# Peripherals_-_USB.net
KiCad netlist of a schematic drawn in Altium Designer
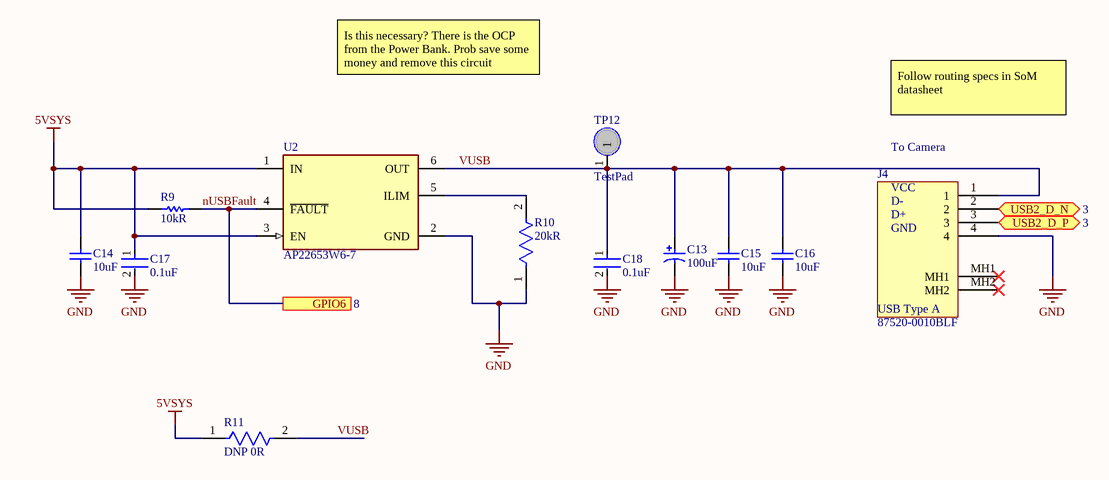
[diagram p0: Peripherals - USB.SchDoc]

(export (version "E")
  (design (tool "Eeschema 10.0.6"))
  (components
    (comp (ref "C13")
      (value "100uF")
      (footprint "PNSC-EEEFK1C101P_L")
      (fields (field (name "MANUFACTURER") "Panasonic"))
      (libsource (lib "Altium Content Vault") (part "CAP-P-2"))
    )
    (comp (ref "C14")
      (value "10uF")
      (footprint "CAPC2013X145X20ML20")
      (fields
        (field (name "MANUFACTURER") "TDK")
        (field (name "TOLERANCE") "±10%")
        (field (name "PCN PART NUMBER") "MLCCPartNumberChange30/Nov/2012")
      )
      (libsource (lib "Altium Content Vault") (part "CAP-NP-2"))
    )
    (comp (ref "C15")
      (value "10uF")
      (footprint "CAPC2013X145X20ML20")
      (fields
        (field (name "MANUFACTURER") "TDK")
        (field (name "TOLERANCE") "±10%")
        (field (name "PCN PART NUMBER") "MLCCPartNumberChange30/Nov/2012")
      )
      (libsource (lib "Altium Content Vault") (part "CAP-NP-2"))
    )
    (comp (ref "C16")
      (value "10uF")
      (footprint "CAPC2013X145X20ML20")
      (fields
        (field (name "MANUFACTURER") "TDK")
        (field (name "TOLERANCE") "±10%")
        (field (name "PCN PART NUMBER") "MLCCPartNumberChange30/Nov/2012")
      )
      (libsource (lib "Altium Content Vault") (part "CAP-NP-2"))
    )
    (comp (ref "C17")
      (value "0.1uF")
      (footprint "FP-C0603-CJ-MFG")
      (description "C0603X104K5RACTU CAP CER 0.1UF 50V X7R 0603")
      (fields (field (name "MANUFACTURER PART NUMBER") "C0603X104K5RACTU") (field (name "VOLTAGE") "50V"))
      (libsource (lib "Altium Content Vault") (part "11868f565c42a9108669ba33697ecf6"))
    )
    (comp (ref "C18")
      (value "0.1uF")
      (footprint "FP-C0603-CJ-MFG")
      (description "C0603X104K5RACTU CAP CER 0.1UF 50V X7R 0603")
      (fields (field (name "MANUFACTURER PART NUMBER") "C0603X104K5RACTU") (field (name "VOLTAGE") "50V"))
      (libsource (lib "Altium Content Vault") (part "11868f565c42a9108669ba33697ecf6"))
    )
    (comp (ref "J4")
      (value "87520-0010BLF")
      (footprint "LayoutFootprintsGoogle:875200010BLF")
      (libsource (lib "SchemSymbolsGoogle") (part "87520-0010BLF"))
    )
    (comp (ref "R9")
      (value "10kR")
      (footprint "RESC2013X60X35NL10T20")
      (fields (field (name "MANUFACTURER") "Yageo"))
      (libsource (lib "Altium Content Vault") (part "RES-2"))
    )
    (comp (ref "R10")
      (value "20kR")
      (footprint "FP-CRCW0805-e3-MFG")
      (description "RES Thick Film, 20kΩ, 1%, 0.125W, 100ppm/°C, 0805")
      (fields (field (name "TOLERANCE") "1%"))
      (libsource (lib "Altium Content Vault") (part "1029c3af85768c4190bb7ad29bc67b5"))
    )
    (comp (ref "R11")
      (value "DNP 0R")
      (footprint "FP-RC1206-MFG")
      (description "RC1206JR-070RL RES SMD 0 OHM JUMPER 1/4W 1206")
      (fields
        (field (name "MANUFACTURER PART NUMBER") "RC1206JR-070RL")
        (field (name "MANUFACTURER") "YAGEO")
      )
      (libsource (lib "Altium Content Vault") (part "1029c3af85768c4190bb7ad29bc67b5"))
    )
    (comp (ref "TP12")
      (value "TestPad")
      (footprint "TestPad50mil")
      (libsource (lib "SchemSymbolsGoogle") (part "TestPad"))
    )
    (comp (ref "U2")
      (value "AP22653W6-7")
      (footprint "FP-SOT26-MFG")
      (description "LOAD SWITCH,SOT26,T&R,3K")
      (libsource (lib "Altium Content Vault") (part "bad2b8b447a47ab10bab651f807ccff"))
    )
  )
  (nets
    (net (code "1") (name "/USB2_D_N") (class "Default")
      (node (ref "J4") (pin "2") (pinfunction "2_2") (pintype "passive"))
    )
    (net (code "2") (name "/USB2_D_P") (class "Default")
      (node (ref "J4") (pin "3") (pinfunction "3_3") (pintype "passive"))
    )
    (net (code "3") (name "/VUSB") (class "Default")
      (node (ref "C13") (pin "1") (pinfunction "1_1") (pintype "passive"))
      (node (ref "C15") (pin "2") (pinfunction "2_2") (pintype "passive"))
      (node (ref "C16") (pin "2") (pinfunction "2_2") (pintype "passive"))
      (node (ref "C18") (pin "1") (pinfunction "1_1") (pintype "passive"))
      (node (ref "J4") (pin "1") (pinfunction "1_1") (pintype "passive"))
      (node (ref "R11") (pin "2") (pinfunction "2_2") (pintype "passive"))
      (node (ref "TP12") (pin "1") (pinfunction "1_1") (pintype "passive"))
      (node (ref "U2") (pin "6") (pinfunction "OUT_6") (pintype "passive"))
    )
    (net (code "4") (name "/nUSBFault") (class "Default")
      (node (ref "R9") (pin "1") (pinfunction "1_1") (pintype "passive"))
      (node (ref "U2") (pin "4") (pinfunction "~{FAULT}_4") (pintype "open_collector"))
    )
    (net (code "5") (name "5VSYS") (class "Default")
      (node (ref "C14") (pin "2") (pinfunction "2_2") (pintype "passive"))
      (node (ref "C17") (pin "1") (pinfunction "1_1") (pintype "passive"))
      (node (ref "R11") (pin "1") (pinfunction "1_1") (pintype "passive"))
      (node (ref "R9") (pin "2") (pinfunction "2_2") (pintype "passive"))
      (node (ref "U2") (pin "1") (pinfunction "IN_1") (pintype "power_in"))
      (node (ref "U2") (pin "3") (pinfunction "EN_3") (pintype "input"))
    )
    (net (code "6") (name "GND") (class "Default")
      (node (ref "C13") (pin "2") (pinfunction "2_2") (pintype "passive"))
      (node (ref "C14") (pin "1") (pinfunction "1_1") (pintype "passive"))
      (node (ref "C15") (pin "1") (pinfunction "1_1") (pintype "passive"))
      (node (ref "C16") (pin "1") (pinfunction "1_1") (pintype "passive"))
      (node (ref "C17") (pin "2") (pinfunction "2_2") (pintype "passive"))
      (node (ref "C18") (pin "2") (pinfunction "2_2") (pintype "passive"))
      (node (ref "J4") (pin "4") (pinfunction "4_4") (pintype "passive"))
      (node (ref "R10") (pin "1") (pinfunction "1_1") (pintype "passive"))
      (node (ref "U2") (pin "2") (pinfunction "GND_2") (pintype "power_in"))
    )
    (net (code "7") (name "Net-(U2-ILIM)") (class "Default")
      (node (ref "R10") (pin "2") (pinfunction "2_2") (pintype "passive"))
      (node (ref "U2") (pin "5") (pinfunction "ILIM_5") (pintype "passive"))
    )
    (net (code "8") (name "unconnected-(J4-PadMH1)") (class "Default")
      (node (ref "J4") (pin "MH1") (pinfunction "MH1_MH1") (pintype "passive+no_connect"))
    )
    (net (code "9") (name "unconnected-(J4-PadMH2)") (class "Default")
      (node (ref "J4") (pin "MH2") (pinfunction "MH2_MH2") (pintype "passive+no_connect"))
    )
  )
)
